# WingboardT.net
KiCad netlist of a schematic drawn in EAGLE
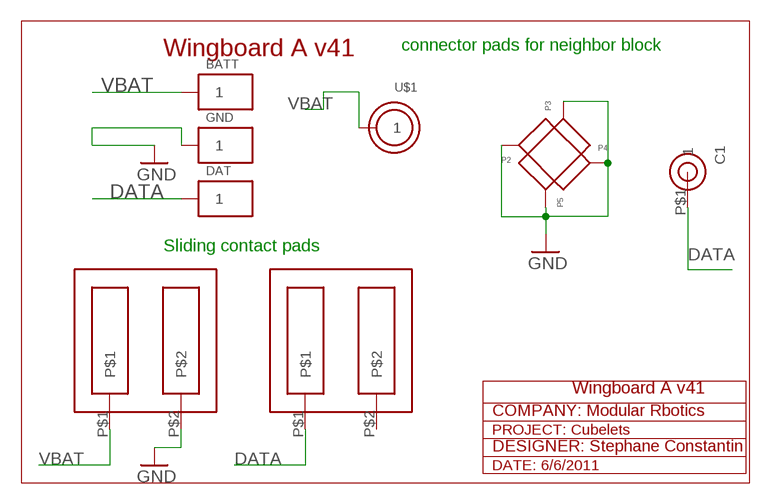
[diagram p0: schematic, sheet 1]

(export (version "E")
  (design (tool "Eeschema 10.0.6"))
  (components
    (comp (ref "BATT")
      (value "PAD2")
      (footprint "eagle-import:PAD2")
      (libsource (lib "eagle-import") (part "PAD2"))
    )
    (comp (ref "C1")
      (value "COMM_PIN2")
      (footprint "eagle-import:COMM_PIN2")
      (libsource (lib "eagle-import") (part "COMM_PIN2"))
    )
    (comp (ref "DAT")
      (value "PAD2")
      (footprint "eagle-import:PAD2")
      (libsource (lib "eagle-import") (part "PAD2"))
    )
    (comp (ref "GND")
      (value "PAD2")
      (footprint "eagle-import:PAD2")
      (libsource (lib "eagle-import") (part "PAD2"))
    )
    (comp (ref "J1")
      (value "SLIDING_CONTACT")
      (footprint "eagle-import:SLIDING_CONTACT")
      (libsource (lib "eagle-import") (part "SLIDING_CONTACT"))
    )
    (comp (ref "J2")
      (value "SLIDING_CONTACT")
      (footprint "eagle-import:SLIDING_CONTACT")
      (libsource (lib "eagle-import") (part "SLIDING_CONTACT"))
    )
    (comp (ref "P2")
      (value "GND_PAD_WING")
      (footprint "eagle-import:GND_PAD_WING")
      (libsource (lib "eagle-import") (part "GND_PAD_WING"))
    )
    (comp (ref "P3")
      (value "GND_PAD_WING")
      (footprint "eagle-import:GND_PAD_WING")
      (libsource (lib "eagle-import") (part "GND_PAD_WING"))
    )
    (comp (ref "P4")
      (value "GND_PAD_WING")
      (footprint "eagle-import:GND_PAD_WING")
      (libsource (lib "eagle-import") (part "GND_PAD_WING"))
    )
    (comp (ref "P5")
      (value "GND_PAD_WING")
      (footprint "eagle-import:GND_PAD_WING")
      (libsource (lib "eagle-import") (part "GND_PAD_WING"))
    )
    (comp (ref "U$1")
      (value "VBAT_CIRCLE")
      (footprint "eagle-import:VBAT_CIRCLE")
      (libsource (lib "eagle-import") (part "VBAT_CIRCLE"))
    )
  )
  (nets
    (net (code "1") (name "/DATA") (class "Default")
      (node (ref "C1") (pin "P$1") (pinfunction "1_P$1") (pintype "bidirectional"))
      (node (ref "DAT") (pin "P$1") (pinfunction "1_P$1") (pintype "bidirectional"))
      (node (ref "J2") (pin "P$1") (pinfunction "P$1_P$1") (pintype "bidirectional"))
    )
    (net (code "2") (name "/VBAT") (class "Default")
      (node (ref "BATT") (pin "P$1") (pinfunction "1_P$1") (pintype "bidirectional"))
      (node (ref "J1") (pin "P$1") (pinfunction "P$1_P$1") (pintype "bidirectional"))
      (node (ref "U$1") (pin "P$1") (pinfunction "1_P$1") (pintype "bidirectional"))
    )
    (net (code "3") (name "GND") (class "Default")
      (node (ref "GND") (pin "P$1") (pinfunction "1_P$1") (pintype "bidirectional"))
      (node (ref "J1") (pin "P$2") (pinfunction "P$2_P$2") (pintype "bidirectional"))
      (node (ref "P2") (pin "P$1") (pinfunction "1_P$1") (pintype "bidirectional"))
      (node (ref "P3") (pin "P$1") (pinfunction "1_P$1") (pintype "bidirectional"))
      (node (ref "P4") (pin "P$1") (pinfunction "1_P$1") (pintype "bidirectional"))
      (node (ref "P5") (pin "P$1") (pinfunction "1_P$1") (pintype "bidirectional"))
    )
    (net (code "4") (name "unconnected-(J2-PadP$2)") (class "Default")
      (node (ref "J2") (pin "P$2") (pinfunction "P$2_P$2") (pintype "bidirectional"))
    )
  )
)
